# light_detector_ALR.net
KiCad netlist of a schematic drawn in EAGLE
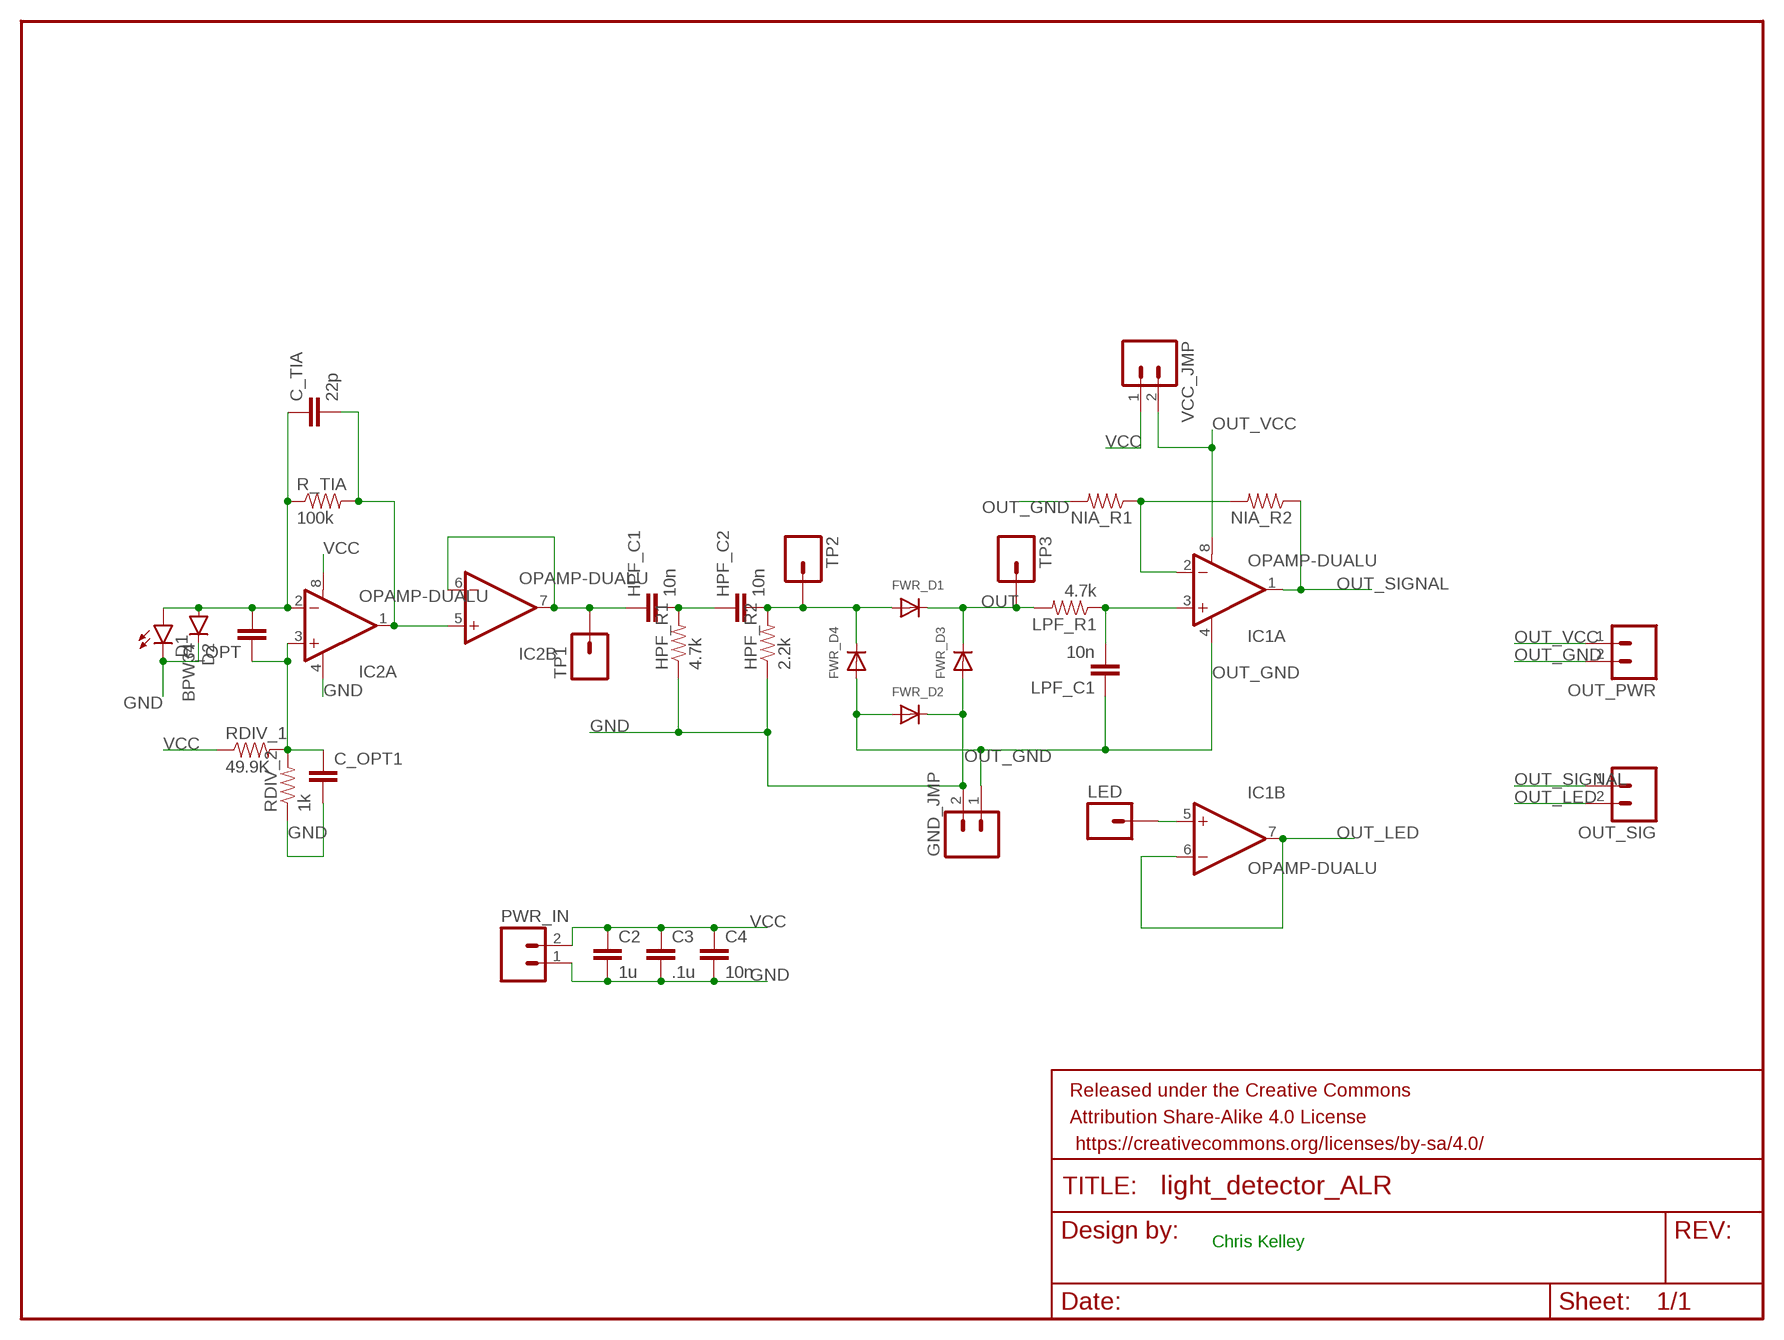
[diagram p0: schematic, sheet 1]

(export (version "E")
  (design (tool "Eeschema 10.0.6"))
  (components
    (comp (ref "C2")
      (value "1u")
      (footprint "eagle-import:0805")
      (libsource (lib "eagle-import") (part "CAP0805"))
    )
    (comp (ref "C3")
      (value ".1u")
      (footprint "eagle-import:0805")
      (libsource (lib "eagle-import") (part "CAP0805"))
    )
    (comp (ref "C4")
      (value "10n")
      (footprint "eagle-import:0805")
      (libsource (lib "eagle-import") (part "CAP0805"))
    )
    (comp (ref "C_OPT")
      (value "CAP0805")
      (footprint "eagle-import:0805")
      (libsource (lib "eagle-import") (part "CAP0805"))
    )
    (comp (ref "C_OPT1")
      (value "CAP0805")
      (footprint "eagle-import:0805")
      (libsource (lib "eagle-import") (part "CAP0805"))
    )
    (comp (ref "C_TIA")
      (value "22p")
      (footprint "eagle-import:0805")
      (libsource (lib "eagle-import") (part "CAP0805"))
    )
    (comp (ref "D1")
      (value "LED5MM")
      (footprint "eagle-import:LED5MM")
      (libsource (lib "eagle-import") (part "LED5MM"))
    )
    (comp (ref "D2")
      (value "BPW34")
      (footprint "eagle-import:BPW34")
      (libsource (lib "eagle-import") (part "BPW34"))
    )
    (comp (ref "FRAME1")
      (value "FRAME-LETTER")
      (footprint "eagle-import:CREATIVE_COMMONS")
      (libsource (lib "eagle-import") (part "FRAME-LETTER"))
    )
    (comp (ref "FWR_D1")
      (value "DIODESOD-123")
      (footprint "eagle-import:SOD-123")
      (libsource (lib "eagle-import") (part "DIODESOD-123"))
    )
    (comp (ref "FWR_D2")
      (value "DIODESOD-123")
      (footprint "eagle-import:SOD-123")
      (libsource (lib "eagle-import") (part "DIODESOD-123"))
    )
    (comp (ref "FWR_D3")
      (value "DIODESOD-123")
      (footprint "eagle-import:SOD-123")
      (libsource (lib "eagle-import") (part "DIODESOD-123"))
    )
    (comp (ref "FWR_D4")
      (value "DIODESOD-123")
      (footprint "eagle-import:SOD-123")
      (libsource (lib "eagle-import") (part "DIODESOD-123"))
    )
    (comp (ref "GND_JMP")
      (value "M02PTH")
      (footprint "eagle-import:1X02")
      (libsource (lib "eagle-import") (part "M02PTH"))
    )
    (comp (ref "HPF_C1")
      (value "10n")
      (footprint "eagle-import:0805")
      (libsource (lib "eagle-import") (part "CAP0805"))
    )
    (comp (ref "HPF_C2")
      (value "10n")
      (footprint "eagle-import:0805")
      (libsource (lib "eagle-import") (part "CAP0805"))
    )
    (comp (ref "HPF_R1")
      (value "4.7k")
      (footprint "eagle-import:0603-RES")
      (libsource (lib "eagle-import") (part "RESISTOR0603-RES"))
    )
    (comp (ref "HPF_R2")
      (value "2.2k")
      (footprint "eagle-import:0603-RES")
      (libsource (lib "eagle-import") (part "RESISTOR0603-RES"))
    )
    (comp (ref "IC1")
      (value "OPAMP-DUALU")
      (footprint "eagle-import:SO08")
      (libsource (lib "eagle-import") (part "OPAMP-DUALU"))
    )
    (comp (ref "IC2")
      (value "OPAMP-DUALU")
      (footprint "eagle-import:SO08")
      (libsource (lib "eagle-import") (part "OPAMP-DUALU"))
    )
    (comp (ref "LED")
      (value "M01PTH")
      (footprint "eagle-import:1X01")
      (libsource (lib "eagle-import") (part "M01PTH"))
    )
    (comp (ref "LPF_C1")
      (value "10n")
      (footprint "eagle-import:0805")
      (libsource (lib "eagle-import") (part "CAP0805"))
    )
    (comp (ref "LPF_R1")
      (value "4.7k")
      (footprint "eagle-import:0603-RES")
      (libsource (lib "eagle-import") (part "RESISTOR0603-RES"))
    )
    (comp (ref "NIA_R1")
      (value "RESISTOR0603-RES")
      (footprint "eagle-import:0603-RES")
      (libsource (lib "eagle-import") (part "RESISTOR0603-RES"))
    )
    (comp (ref "NIA_R2")
      (value "RESISTOR0603-RES")
      (footprint "eagle-import:0603-RES")
      (libsource (lib "eagle-import") (part "RESISTOR0603-RES"))
    )
    (comp (ref "OUT_PWR")
      (value "M02PTH")
      (footprint "eagle-import:1X02")
      (libsource (lib "eagle-import") (part "M02PTH"))
    )
    (comp (ref "OUT_SIG")
      (value "M02PTH")
      (footprint "eagle-import:1X02")
      (libsource (lib "eagle-import") (part "M02PTH"))
    )
    (comp (ref "PWR_IN")
      (value "M02PTH")
      (footprint "eagle-import:1X02")
      (libsource (lib "eagle-import") (part "M02PTH"))
    )
    (comp (ref "RDIV_1")
      (value "49.9K")
      (footprint "eagle-import:0603-RES")
      (libsource (lib "eagle-import") (part "RESISTOR0603-RES"))
    )
    (comp (ref "RDIV_2")
      (value "1k")
      (footprint "eagle-import:0603-RES")
      (libsource (lib "eagle-import") (part "RESISTOR0603-RES"))
    )
    (comp (ref "R_TIA")
      (value "100k")
      (footprint "eagle-import:0603-RES")
      (libsource (lib "eagle-import") (part "RESISTOR0603-RES"))
    )
    (comp (ref "TP1")
      (value "M01PTH")
      (footprint "eagle-import:1X01")
      (libsource (lib "eagle-import") (part "M01PTH"))
    )
    (comp (ref "TP2")
      (value "M01PTH")
      (footprint "eagle-import:1X01")
      (libsource (lib "eagle-import") (part "M01PTH"))
    )
    (comp (ref "TP3")
      (value "M01PTH")
      (footprint "eagle-import:1X01")
      (libsource (lib "eagle-import") (part "M01PTH"))
    )
    (comp (ref "VCC_JMP")
      (value "M02PTH")
      (footprint "eagle-import:1X02")
      (libsource (lib "eagle-import") (part "M02PTH"))
    )
  )
  (nets
    (net (code "1") (name "/GND") (class "Default")
      (node (ref "C2") (pin "2") (pinfunction "2_2") (pintype "passive"))
      (node (ref "C3") (pin "2") (pinfunction "2_2") (pintype "passive"))
      (node (ref "C4") (pin "2") (pinfunction "2_2") (pintype "passive"))
      (node (ref "C_OPT1") (pin "2") (pinfunction "2_2") (pintype "passive"))
      (node (ref "D1") (pin "K") (pinfunction "C_K") (pintype "passive"))
      (node (ref "D2") (pin "P$2") (pinfunction "C_P$2") (pintype "passive"))
      (node (ref "FWR_D2") (pin "C") (pinfunction "C_C") (pintype "passive"))
      (node (ref "FWR_D3") (pin "A") (pinfunction "A_A") (pintype "passive"))
      (node (ref "GND_JMP") (pin "2") (pinfunction "2_2") (pintype "passive"))
      (node (ref "HPF_R1") (pin "1") (pinfunction "1_1") (pintype "passive"))
      (node (ref "HPF_R2") (pin "1") (pinfunction "1_1") (pintype "passive"))
      (node (ref "IC2") (pin "4") (pinfunction "V-_4") (pintype "power_in"))
      (node (ref "PWR_IN") (pin "1") (pinfunction "1_1") (pintype "passive"))
      (node (ref "RDIV_2") (pin "1") (pinfunction "1_1") (pintype "passive"))
    )
    (net (code "2") (name "/OUT") (class "Default")
      (node (ref "FWR_D1") (pin "C") (pinfunction "C_C") (pintype "passive"))
      (node (ref "FWR_D3") (pin "C") (pinfunction "C_C") (pintype "passive"))
      (node (ref "LPF_R1") (pin "2") (pinfunction "2_2") (pintype "passive"))
      (node (ref "TP3") (pin "1") (pinfunction "1_1") (pintype "passive"))
    )
    (net (code "3") (name "/OUT_GND") (class "Default")
      (node (ref "FWR_D2") (pin "A") (pinfunction "A_A") (pintype "passive"))
      (node (ref "FWR_D4") (pin "A") (pinfunction "A_A") (pintype "passive"))
      (node (ref "GND_JMP") (pin "1") (pinfunction "1_1") (pintype "passive"))
      (node (ref "IC1") (pin "4") (pinfunction "V-_4") (pintype "power_in"))
      (node (ref "LPF_C1") (pin "1") (pinfunction "1_1") (pintype "passive"))
      (node (ref "NIA_R1") (pin "2") (pinfunction "2_2") (pintype "passive"))
      (node (ref "OUT_PWR") (pin "2") (pinfunction "2_2") (pintype "passive"))
    )
    (net (code "4") (name "/OUT_LED") (class "Default")
      (node (ref "IC1") (pin "6") (pinfunction "-IN_6") (pintype "input"))
      (node (ref "IC1") (pin "7") (pinfunction "OUT_7") (pintype "output"))
      (node (ref "OUT_SIG") (pin "2") (pinfunction "2_2") (pintype "passive"))
    )
    (net (code "5") (name "/OUT_SIGNAL") (class "Default")
      (node (ref "IC1") (pin "1") (pinfunction "OUT_1") (pintype "output"))
      (node (ref "NIA_R2") (pin "1") (pinfunction "1_1") (pintype "passive"))
      (node (ref "OUT_SIG") (pin "1") (pinfunction "1_1") (pintype "passive"))
    )
    (net (code "6") (name "/OUT_VCC") (class "Default")
      (node (ref "IC1") (pin "8") (pinfunction "V+_8") (pintype "power_in"))
      (node (ref "OUT_PWR") (pin "1") (pinfunction "1_1") (pintype "passive"))
      (node (ref "VCC_JMP") (pin "2") (pinfunction "2_2") (pintype "passive"))
    )
    (net (code "7") (name "/VCC") (class "Default")
      (node (ref "C2") (pin "1") (pinfunction "1_1") (pintype "passive"))
      (node (ref "C3") (pin "1") (pinfunction "1_1") (pintype "passive"))
      (node (ref "C4") (pin "1") (pinfunction "1_1") (pintype "passive"))
      (node (ref "IC2") (pin "8") (pinfunction "V+_8") (pintype "power_in"))
      (node (ref "PWR_IN") (pin "2") (pinfunction "2_2") (pintype "passive"))
      (node (ref "RDIV_1") (pin "1") (pinfunction "1_1") (pintype "passive"))
      (node (ref "VCC_JMP") (pin "1") (pinfunction "1_1") (pintype "passive"))
    )
    (net (code "8") (name "Net-(D2-A)") (class "Default")
      (node (ref "C_OPT") (pin "2") (pinfunction "2_2") (pintype "passive"))
      (node (ref "C_TIA") (pin "1") (pinfunction "1_1") (pintype "passive"))
      (node (ref "D1") (pin "A") (pinfunction "A_A") (pintype "passive"))
      (node (ref "D2") (pin "P$1") (pinfunction "A_P$1") (pintype "passive"))
      (node (ref "IC2") (pin "2") (pinfunction "-IN_2") (pintype "input"))
      (node (ref "R_TIA") (pin "1") (pinfunction "1_1") (pintype "passive"))
    )
    (net (code "9") (name "Net-(FWR_D1-PadA)") (class "Default")
      (node (ref "FWR_D1") (pin "A") (pinfunction "A_A") (pintype "passive"))
      (node (ref "FWR_D4") (pin "C") (pinfunction "C_C") (pintype "passive"))
      (node (ref "HPF_C2") (pin "2") (pinfunction "2_2") (pintype "passive"))
      (node (ref "HPF_R2") (pin "2") (pinfunction "2_2") (pintype "passive"))
      (node (ref "TP2") (pin "1") (pinfunction "1_1") (pintype "passive"))
    )
    (net (code "10") (name "Net-(HPF_C1-Pad2)") (class "Default")
      (node (ref "HPF_C1") (pin "2") (pinfunction "2_2") (pintype "passive"))
      (node (ref "HPF_C2") (pin "1") (pinfunction "1_1") (pintype "passive"))
      (node (ref "HPF_R1") (pin "2") (pinfunction "2_2") (pintype "passive"))
    )
    (net (code "11") (name "Net-(IC1A-+IN)") (class "Default")
      (node (ref "IC1") (pin "3") (pinfunction "+IN_3") (pintype "input"))
      (node (ref "LPF_C1") (pin "2") (pinfunction "2_2") (pintype "passive"))
      (node (ref "LPF_R1") (pin "1") (pinfunction "1_1") (pintype "passive"))
    )
    (net (code "12") (name "Net-(IC1A--IN)") (class "Default")
      (node (ref "IC1") (pin "2") (pinfunction "-IN_2") (pintype "input"))
      (node (ref "NIA_R1") (pin "1") (pinfunction "1_1") (pintype "passive"))
      (node (ref "NIA_R2") (pin "2") (pinfunction "2_2") (pintype "passive"))
    )
    (net (code "13") (name "Net-(IC1B-+IN)") (class "Default")
      (node (ref "IC1") (pin "5") (pinfunction "+IN_5") (pintype "input"))
      (node (ref "LED") (pin "1") (pinfunction "1_1") (pintype "passive"))
    )
    (net (code "14") (name "Net-(IC2A-+IN)") (class "Default")
      (node (ref "C_OPT") (pin "1") (pinfunction "1_1") (pintype "passive"))
      (node (ref "C_OPT1") (pin "1") (pinfunction "1_1") (pintype "passive"))
      (node (ref "IC2") (pin "3") (pinfunction "+IN_3") (pintype "input"))
      (node (ref "RDIV_1") (pin "2") (pinfunction "2_2") (pintype "passive"))
      (node (ref "RDIV_2") (pin "2") (pinfunction "2_2") (pintype "passive"))
    )
    (net (code "15") (name "Net-(IC2A-OUT)") (class "Default")
      (node (ref "C_TIA") (pin "2") (pinfunction "2_2") (pintype "passive"))
      (node (ref "IC2") (pin "1") (pinfunction "OUT_1") (pintype "output"))
      (node (ref "IC2") (pin "5") (pinfunction "+IN_5") (pintype "input"))
      (node (ref "R_TIA") (pin "2") (pinfunction "2_2") (pintype "passive"))
    )
    (net (code "16") (name "Net-(IC2B--IN)") (class "Default")
      (node (ref "HPF_C1") (pin "1") (pinfunction "1_1") (pintype "passive"))
      (node (ref "IC2") (pin "6") (pinfunction "-IN_6") (pintype "input"))
      (node (ref "IC2") (pin "7") (pinfunction "OUT_7") (pintype "output"))
      (node (ref "TP1") (pin "1") (pinfunction "1_1") (pintype "passive"))
    )
  )
)
